# Power2.net
KiCad netlist of a schematic drawn in Altium Designer
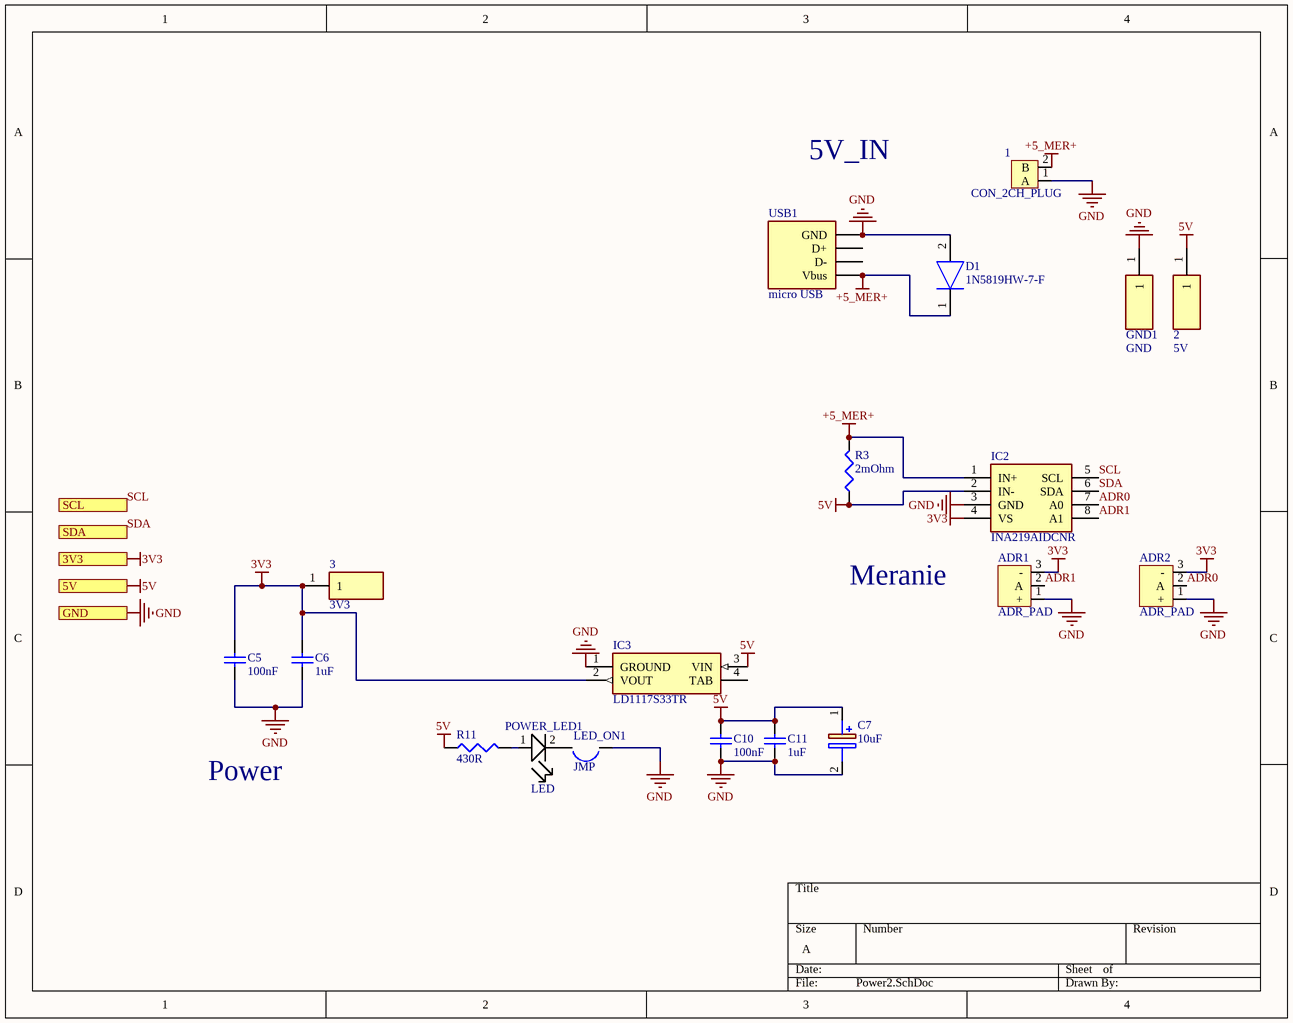
[diagram p0: Power2.SchDoc]

(export (version "E")
  (design (tool "Eeschema 10.0.6"))
  (components
    (comp (ref "1")
      (value "CON_2CH_PLUG")
      (footprint "CON_2CH_PLUG")
      (description "TBG-5.0-KW-2P")
      (libsource (lib "SCH_Aquatec") (part "CON_2CH_PLUG"))
    )
    (comp (ref "2")
      (value "5V")
      (footprint "1508000150000030")
      (description "Undefined or Miscellaneous")
      (fields (field (name "MANUFACTURER_PART_NUMBER") "5015") (field (name "MOUSER PART NUMBER") "534-5015"))
      (libsource (lib "*") (part "5015"))
    )
    (comp (ref "3")
      (value "3V3")
      (footprint "1508000150000030")
      (description "Undefined or Miscellaneous")
      (fields (field (name "MANUFACTURER_PART_NUMBER") "5015") (field (name "MOUSER PART NUMBER") "534-5015"))
      (libsource (lib "") (part "5015_1"))
    )
    (comp (ref "ADR1")
      (value "ADR_PAD")
      (footprint "SOLDER_PAD")
      (description "ADR PAD 3 PIN")
      (libsource (lib "SCH_Aquatec") (part "ADR_PAD"))
    )
    (comp (ref "ADR2")
      (value "ADR_PAD")
      (footprint "SOLDER_PAD")
      (description "ADR PAD 3 PIN")
      (libsource (lib "SCH_Aquatec") (part "ADR_PAD"))
    )
    (comp (ref "C5")
      (value "100nF")
      (footprint "1608[0603]")
      (description "Capacitor")
      (fields (field (name "PUBLISHER") "Altium Limited"))
      (libsource (lib "Miscellaneous Devices") (part "Cap Semi"))
    )
    (comp (ref "C6")
      (value "1uF")
      (footprint "1608[0603]")
      (description "Capacitor")
      (fields (field (name "PUBLISHER") "Altium Limited"))
      (libsource (lib "Miscellaneous Devices") (part "Cap Semi"))
    )
    (comp (ref "C7")
      (value "10uF")
      (footprint "CAPPM3216X180N")
      (description "Capacitor Polarised")
      (fields
        (field (name "MANUFACTURER_PART_NUMBER") "TAJA106K004RNJ")
        (field (name "MOUSER PART NUMBER") "581-TAJA106K004R")
      )
      (libsource (lib "*") (part "TAJA106K004RNJ"))
    )
    (comp (ref "C10")
      (value "100nF")
      (footprint "1608[0603]")
      (description "Capacitor")
      (fields (field (name "PUBLISHER") "Altium Limited"))
      (libsource (lib "Miscellaneous Devices") (part "Cap Semi"))
    )
    (comp (ref "C11")
      (value "1uF")
      (footprint "1608[0603]")
      (description "Capacitor")
      (fields (field (name "PUBLISHER") "Altium Limited"))
      (libsource (lib "Miscellaneous Devices") (part "Cap Semi"))
    )
    (comp (ref "D1")
      (value "1N5819HW-7-F")
      (footprint "SamacSys:SOD3716X145N")
      (description "Diode")
      (fields (field (name "MOUSER PART NUMBER") "621-1N5819HW-F"))
      (libsource (lib "*") (part "1N5819HW-7-F"))
    )
    (comp (ref "GND1")
      (value "GND")
      (footprint "1508000150000030")
      (description "Undefined or Miscellaneous")
      (fields (field (name "MANUFACTURER_PART_NUMBER") "5015") (field (name "MOUSER PART NUMBER") "534-5015"))
      (libsource (lib "*") (part "5015"))
    )
    (comp (ref "IC2")
      (value "INA219AIDCNR")
      (footprint "SOT65P280X145-8N")
      (description "Integrated Circuit")
      (fields
        (field (name "MANUFACTURER_PART_NUMBER") "INA219BIDCNR")
        (field (name "MOUSER PART NUMBER") "595-INA219BIDCNR")
      )
      (libsource (lib "*") (part "INA219BIDCNR"))
    )
    (comp (ref "IC3")
      (value "LD1117S33TR")
      (footprint "SOT230P700X180-4N")
      (description "Integrated Circuit")
      (fields (field (name "MOUSER PART NUMBER") "511-LD1117S33") (field (name "RS PART NUMBER") "7140697P"))
      (libsource (lib "*") (part "LD1117S33TR"))
    )
    (comp (ref "LED_ON1") (value "JMP") (footprint "JMP") (libsource (lib "SamacSys") (part "JMP")))
    (comp (ref "POWER_LED1")
      (value "LED")
      (footprint "LED5mA")
      (libsource (lib "SchematicLib_JP") (part "LED"))
    )
    (comp (ref "R3")
      (value "2mOhm")
      (footprint "RESC3216X75N")
      (description "Resistor")
      (fields (field (name "PUBLISHER") "Altium Limited"))
      (libsource (lib "Miscellaneous Devices") (part "Res3"))
    )
    (comp (ref "R11")
      (value "430R")
      (footprint "J1-0603")
      (description "Resistor")
      (fields (field (name "PUBLISHER") "Altium Limited"))
      (libsource (lib "Miscellaneous Devices") (part "Res3"))
    )
    (comp (ref "USB1")
      (value "micro USB")
      (footprint "micro USB")
      (libsource (lib "SamacSys") (part "micro USB"))
    )
  )
  (nets
    (net (code "1") (name "+5_MER+") (class "Default")
      (node (ref "1") (pin "2") (pinfunction "B_2") (pintype "passive"))
      (node (ref "D1") (pin "1") (pinfunction "K_1") (pintype "passive"))
      (node (ref "IC2") (pin "1") (pinfunction "IN+_1") (pintype "passive"))
      (node (ref "R3") (pin "2") (pinfunction "2_2") (pintype "passive"))
      (node (ref "USB1") (pin "1") (pinfunction "Vbus_1") (pintype "passive"))
    )
    (net (code "2") (name "/ADR0") (class "Default")
      (node (ref "ADR2") (pin "2") (pinfunction "A_2") (pintype "passive"))
      (node (ref "IC2") (pin "7") (pinfunction "A0_7") (pintype "passive"))
    )
    (net (code "3") (name "/ADR1") (class "Default")
      (node (ref "ADR1") (pin "2") (pinfunction "A_2") (pintype "passive"))
      (node (ref "IC2") (pin "8") (pinfunction "A1_8") (pintype "passive"))
    )
    (net (code "4") (name "/SCL") (class "Default")
      (node (ref "IC2") (pin "5") (pinfunction "SCL_5") (pintype "passive"))
    )
    (net (code "5") (name "/SDA") (class "Default")
      (node (ref "IC2") (pin "6") (pinfunction "SDA_6") (pintype "passive"))
    )
    (net (code "6") (name "3V3") (class "Default")
      (node (ref "3") (pin "1") (pinfunction "1_1") (pintype "passive"))
      (node (ref "ADR1") (pin "3") (pinfunction "-_3") (pintype "passive"))
      (node (ref "ADR2") (pin "3") (pinfunction "-_3") (pintype "passive"))
      (node (ref "C5") (pin "1") (pinfunction "1_1") (pintype "passive"))
      (node (ref "C6") (pin "1") (pinfunction "1_1") (pintype "passive"))
      (node (ref "IC2") (pin "4") (pinfunction "VS_4") (pintype "power_in"))
      (node (ref "IC3") (pin "2") (pinfunction "VOUT_2") (pintype "output"))
    )
    (net (code "7") (name "5V") (class "Default")
      (node (ref "2") (pin "1") (pinfunction "1_1") (pintype "passive"))
      (node (ref "C10") (pin "1") (pinfunction "1_1") (pintype "passive"))
      (node (ref "C11") (pin "1") (pinfunction "1_1") (pintype "passive"))
      (node (ref "C7") (pin "1") (pinfunction "+_1") (pintype "passive"))
      (node (ref "IC2") (pin "2") (pinfunction "IN-_2") (pintype "passive"))
      (node (ref "IC3") (pin "3") (pinfunction "VIN_3") (pintype "input"))
      (node (ref "R11") (pin "1") (pinfunction "1_1") (pintype "passive"))
      (node (ref "R3") (pin "1") (pinfunction "1_1") (pintype "passive"))
    )
    (net (code "8") (name "GND") (class "Default")
      (node (ref "1") (pin "1") (pinfunction "A_1") (pintype "passive"))
      (node (ref "ADR1") (pin "1") (pinfunction "+_1") (pintype "passive"))
      (node (ref "ADR2") (pin "1") (pinfunction "+_1") (pintype "passive"))
      (node (ref "C10") (pin "2") (pinfunction "2_2") (pintype "passive"))
      (node (ref "C11") (pin "2") (pinfunction "2_2") (pintype "passive"))
      (node (ref "C5") (pin "2") (pinfunction "2_2") (pintype "passive"))
      (node (ref "C6") (pin "2") (pinfunction "2_2") (pintype "passive"))
      (node (ref "C7") (pin "2") (pinfunction "-_2") (pintype "passive"))
      (node (ref "D1") (pin "2") (pinfunction "A_2") (pintype "passive"))
      (node (ref "GND1") (pin "1") (pinfunction "1_1") (pintype "passive"))
      (node (ref "IC2") (pin "3") (pinfunction "GND_3") (pintype "power_in"))
      (node (ref "IC3") (pin "1") (pinfunction "GROUND_1") (pintype "passive"))
      (node (ref "LED_ON1") (pin "1") (pinfunction "1_1") (pintype "passive"))
      (node (ref "USB1") (pin "5") (pinfunction "GND_5") (pintype "passive"))
    )
    (net (code "9") (name "Net-(LED_ON1-Pad2)") (class "Default")
      (node (ref "LED_ON1") (pin "2") (pinfunction "2_2") (pintype "passive"))
      (node (ref "POWER_LED1") (pin "2") (pinfunction "2_2") (pintype "passive"))
    )
    (net (code "10") (name "Net-(POWER_LED1-Pad1)") (class "Default")
      (node (ref "POWER_LED1") (pin "1") (pinfunction "1_1") (pintype "passive"))
      (node (ref "R11") (pin "2") (pinfunction "2_2") (pintype "passive"))
    )
    (net (code "11") (name "unconnected-(IC3-TAB-Pad4)") (class "Default")
      (node (ref "IC3") (pin "4") (pinfunction "TAB_4") (pintype "passive"))
    )
    (net (code "12") (name "unconnected-(USB1-D+-Pad3)") (class "Default")
      (node (ref "USB1") (pin "3") (pinfunction "D+_3") (pintype "passive"))
    )
    (net (code "13") (name "unconnected-(USB1-D--Pad2)") (class "Default")
      (node (ref "USB1") (pin "2") (pinfunction "D-_2") (pintype "passive"))
    )
  )
)
